# kulgurpowerMCU.net
KiCad netlist of a schematic drawn in EAGLE
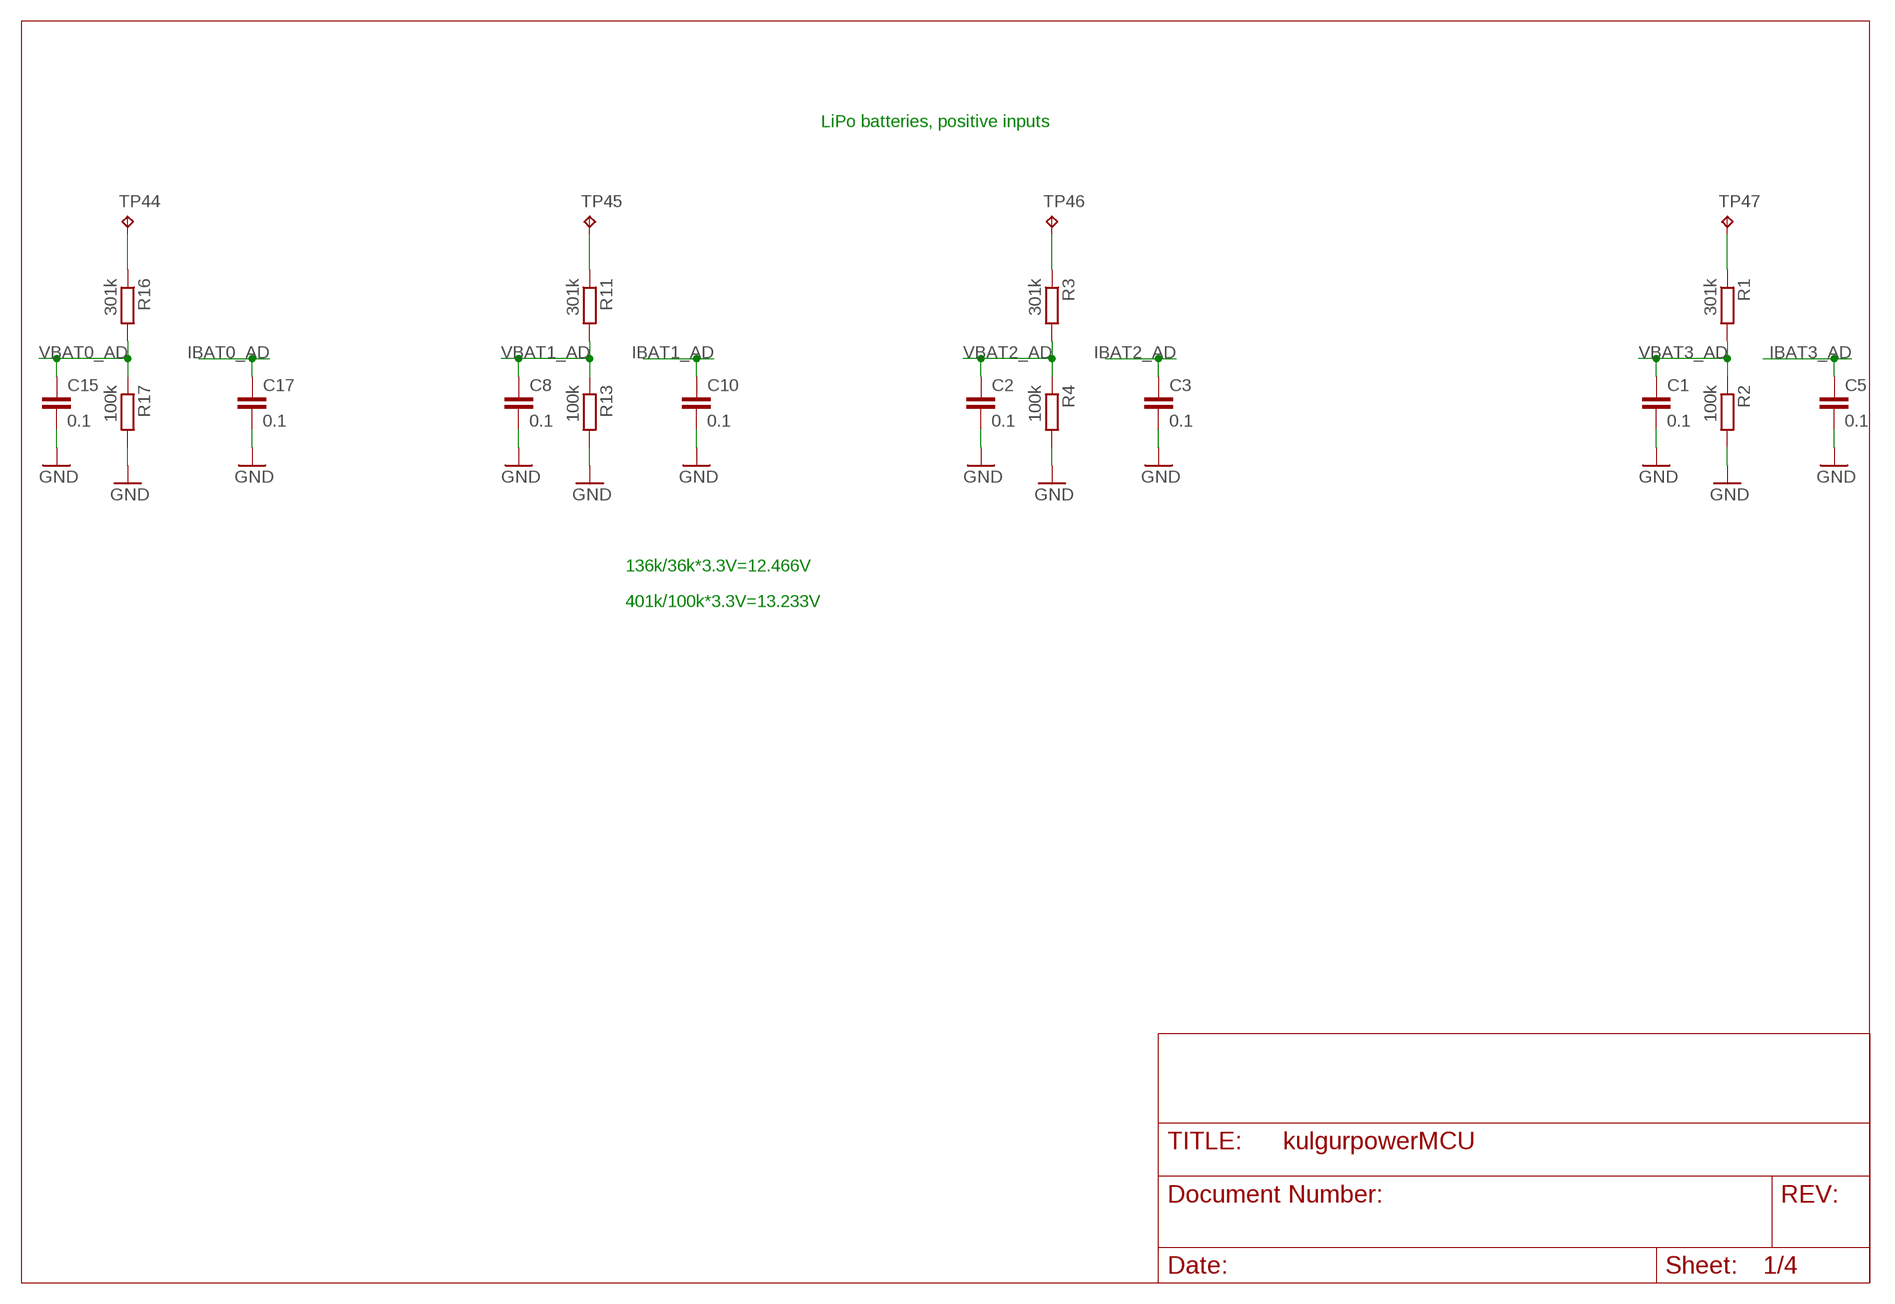
[diagram p0: schematic, sheet 1]
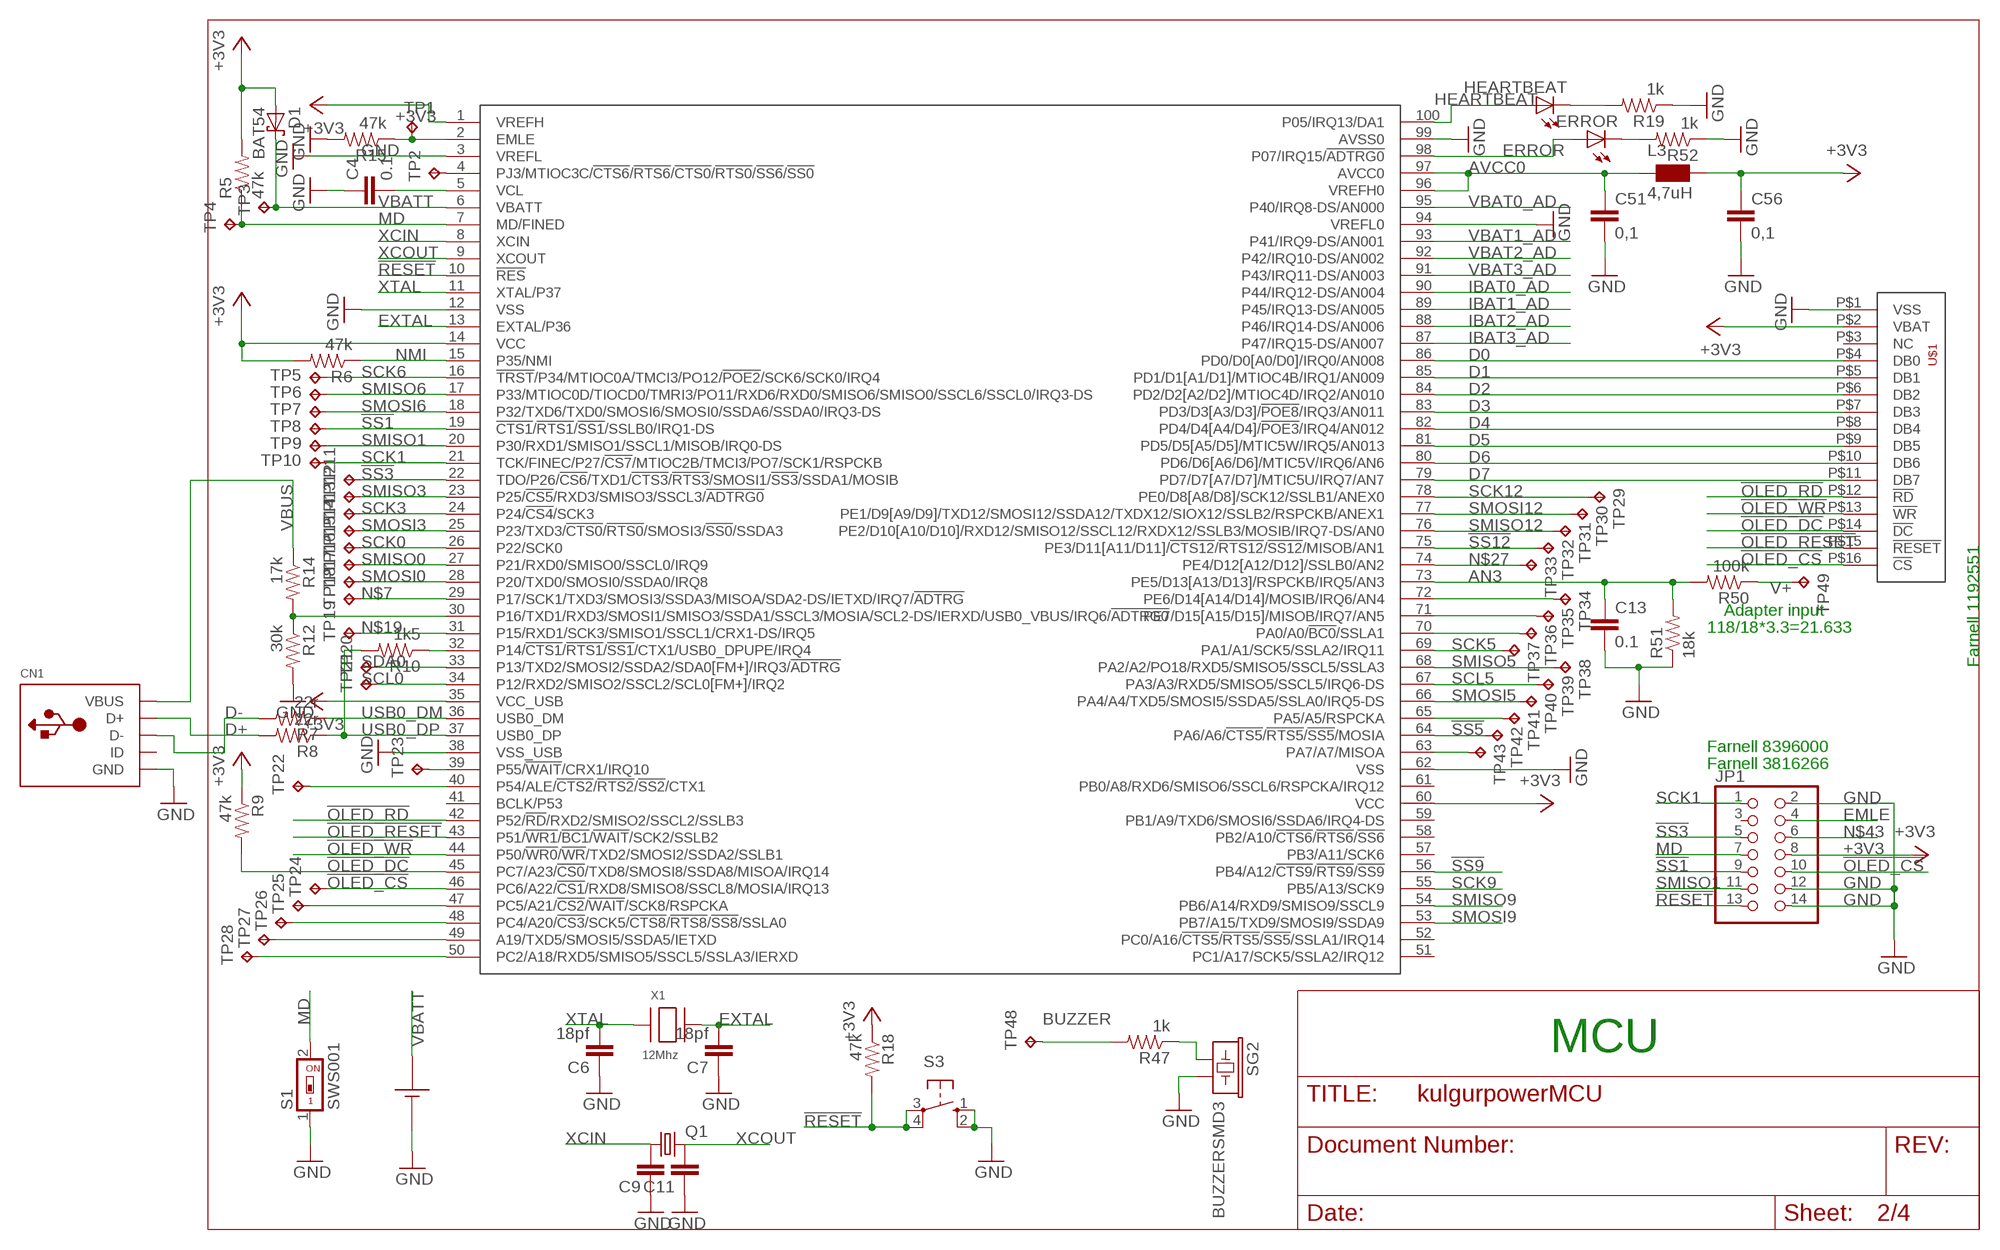
[diagram p1: schematic, sheet 2]
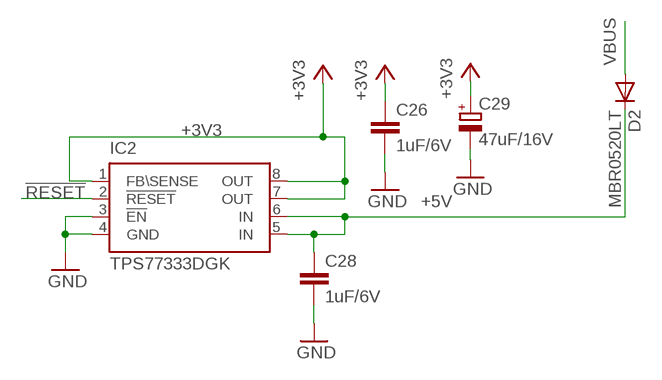
[diagram p2: schematic, sheet 3]

(export (version "E")
  (design (tool "Eeschema 10.0.6"))
  (components
    (comp (ref "C4")
      (value "0.1")
      (footprint "eagle-import:0603-CAP")
      (libsource (lib "eagle-import") (part "CAP0603-CAP"))
    )
    (comp (ref "C6")
      (value "18pf")
      (footprint "eagle-import:0603-CAP")
      (libsource (lib "eagle-import") (part "CAP0603-CAP"))
    )
    (comp (ref "C7")
      (value "18pf")
      (footprint "eagle-import:0603-CAP")
      (libsource (lib "eagle-import") (part "CAP0603-CAP"))
    )
    (comp (ref "C9")
      (value "CAP0603-CAP")
      (footprint "eagle-import:0603-CAP")
      (libsource (lib "eagle-import") (part "CAP0603-CAP"))
    )
    (comp (ref "C11")
      (value "CAP0603-CAP")
      (footprint "eagle-import:0603-CAP")
      (libsource (lib "eagle-import") (part "CAP0603-CAP"))
    )
    (comp (ref "C13")
      (value "0.1")
      (footprint "eagle-import:0603-CAP")
      (libsource (lib "eagle-import") (part "CAP0603-CAP"))
    )
    (comp (ref "C51")
      (value "0,1")
      (footprint "eagle-import:0603-CAP")
      (libsource (lib "eagle-import") (part "CAP0603-CAP"))
    )
    (comp (ref "C56")
      (value "0,1")
      (footprint "eagle-import:0603-CAP")
      (libsource (lib "eagle-import") (part "CAP0603-CAP"))
    )
    (comp (ref "CN1")
      (value "USBMINIB")
      (footprint "eagle-import:USB-MINIB")
      (libsource (lib "eagle-import") (part "USBMINIB"))
    )
    (comp (ref "D1")
      (value "BAT54")
      (footprint "eagle-import:SOT23")
      (libsource (lib "eagle-import") (part "BAT54"))
    )
    (comp (ref "ERROR")
      (value "LED0603")
      (footprint "eagle-import:LED-0603")
      (libsource (lib "eagle-import") (part "LED0603"))
    )
    (comp (ref "HEARTBEAT")
      (value "LED0603")
      (footprint "eagle-import:LED-0603")
      (libsource (lib "eagle-import") (part "LED0603"))
    )
    (comp (ref "JP1")
      (value "PINHD-2X7")
      (footprint "eagle-import:2X07")
      (libsource (lib "eagle-import") (part "PINHD-2X7"))
    )
    (comp (ref "L3")
      (value "4,7uH")
      (footprint "eagle-import:WE-KI_0805_B")
      (libsource (lib "eagle-import") (part "WE-KIHQ_0805"))
    )
    (comp (ref "Q1")
      (value "CRYSTALMM20SS")
      (footprint "eagle-import:MM20SS")
      (libsource (lib "eagle-import") (part "CRYSTALMM20SS"))
    )
    (comp (ref "R5")
      (value "47k")
      (footprint "eagle-import:0603-RES")
      (libsource (lib "eagle-import") (part "RESISTOR0603-RES"))
    )
    (comp (ref "R6")
      (value "47k")
      (footprint "eagle-import:0603-RES")
      (libsource (lib "eagle-import") (part "RESISTOR0603-RES"))
    )
    (comp (ref "R7")
      (value "22r")
      (footprint "eagle-import:0603-RES")
      (libsource (lib "eagle-import") (part "RESISTOR0603-RES"))
    )
    (comp (ref "R8")
      (value "22r")
      (footprint "eagle-import:0603-RES")
      (libsource (lib "eagle-import") (part "RESISTOR0603-RES"))
    )
    (comp (ref "R9")
      (value "47k")
      (footprint "eagle-import:0603-RES")
      (libsource (lib "eagle-import") (part "RESISTOR0603-RES"))
    )
    (comp (ref "R10")
      (value "1k5")
      (footprint "eagle-import:0603-RES")
      (libsource (lib "eagle-import") (part "RESISTOR0603-RES"))
    )
    (comp (ref "R12")
      (value "30k")
      (footprint "eagle-import:0603-RES")
      (libsource (lib "eagle-import") (part "RESISTOR0603-RES"))
    )
    (comp (ref "R14")
      (value "17k")
      (footprint "eagle-import:0603-RES")
      (libsource (lib "eagle-import") (part "RESISTOR0603-RES"))
    )
    (comp (ref "R15")
      (value "47k")
      (footprint "eagle-import:0603-RES")
      (libsource (lib "eagle-import") (part "RESISTOR0603-RES"))
    )
    (comp (ref "R18")
      (value "47k")
      (footprint "eagle-import:0603-RES")
      (libsource (lib "eagle-import") (part "RESISTOR0603-RES"))
    )
    (comp (ref "R19")
      (value "1k")
      (footprint "eagle-import:0603-RES")
      (libsource (lib "eagle-import") (part "RESISTOR0603-RES"))
    )
    (comp (ref "R47")
      (value "1k")
      (footprint "eagle-import:0603-RES")
      (libsource (lib "eagle-import") (part "RESISTOR0603-RES"))
    )
    (comp (ref "R50")
      (value "100k")
      (footprint "eagle-import:0603-RES")
      (libsource (lib "eagle-import") (part "RESISTOR0603-RES"))
    )
    (comp (ref "R51")
      (value "18k")
      (footprint "eagle-import:0603-RES")
      (libsource (lib "eagle-import") (part "RESISTOR0603-RES"))
    )
    (comp (ref "R52")
      (value "1k")
      (footprint "eagle-import:0603-RES")
      (libsource (lib "eagle-import") (part "RESISTOR0603-RES"))
    )
    (comp (ref "S1")
      (value "SWS001")
      (footprint "eagle-import:SMS-001")
      (libsource (lib "eagle-import") (part "SWS001"))
    )
    (comp (ref "S3")
      (value "10-XX")
      (footprint "eagle-import:B3F-10XX")
      (fields (field (name "MPN") "B3F-1000"))
      (libsource (lib "eagle-import") (part "10-XX"))
    )
    (comp (ref "SG2")
      (value "BUZZERSMD3")
      (footprint "eagle-import:BUZZER-CMT1102")
      (libsource (lib "eagle-import") (part "BUZZERSMD3"))
    )
    (comp (ref "TP1")
      (value "TPB2,54")
      (footprint "eagle-import:B2,54")
      (libsource (lib "eagle-import") (part "TPB2,54"))
    )
    (comp (ref "TP2")
      (value "TPB2,54")
      (footprint "eagle-import:B2,54")
      (libsource (lib "eagle-import") (part "TPB2,54"))
    )
    (comp (ref "TP3")
      (value "TPB2,54")
      (footprint "eagle-import:B2,54")
      (libsource (lib "eagle-import") (part "TPB2,54"))
    )
    (comp (ref "TP4")
      (value "TPB2,54")
      (footprint "eagle-import:B2,54")
      (libsource (lib "eagle-import") (part "TPB2,54"))
    )
    (comp (ref "TP5")
      (value "TPB1,27")
      (footprint "eagle-import:B1,27")
      (libsource (lib "eagle-import") (part "TPB1,27"))
    )
    (comp (ref "TP6")
      (value "TPB1,27")
      (footprint "eagle-import:B1,27")
      (libsource (lib "eagle-import") (part "TPB1,27"))
    )
    (comp (ref "TP7")
      (value "TPB1,27")
      (footprint "eagle-import:B1,27")
      (libsource (lib "eagle-import") (part "TPB1,27"))
    )
    (comp (ref "TP8")
      (value "TPB1,27")
      (footprint "eagle-import:B1,27")
      (libsource (lib "eagle-import") (part "TPB1,27"))
    )
    (comp (ref "TP9")
      (value "TPB1,27")
      (footprint "eagle-import:B1,27")
      (libsource (lib "eagle-import") (part "TPB1,27"))
    )
    (comp (ref "TP10")
      (value "TPB1,27")
      (footprint "eagle-import:B1,27")
      (libsource (lib "eagle-import") (part "TPB1,27"))
    )
    (comp (ref "TP11")
      (value "TPB1,27")
      (footprint "eagle-import:B1,27")
      (libsource (lib "eagle-import") (part "TPB1,27"))
    )
    (comp (ref "TP12")
      (value "TPB1,27")
      (footprint "eagle-import:B1,27")
      (libsource (lib "eagle-import") (part "TPB1,27"))
    )
    (comp (ref "TP13")
      (value "TPB1,27")
      (footprint "eagle-import:B1,27")
      (libsource (lib "eagle-import") (part "TPB1,27"))
    )
    (comp (ref "TP14")
      (value "TPB1,27")
      (footprint "eagle-import:B1,27")
      (libsource (lib "eagle-import") (part "TPB1,27"))
    )
    (comp (ref "TP15")
      (value "TPB1,27")
      (footprint "eagle-import:B1,27")
      (libsource (lib "eagle-import") (part "TPB1,27"))
    )
    (comp (ref "TP16")
      (value "TPB1,27")
      (footprint "eagle-import:B1,27")
      (libsource (lib "eagle-import") (part "TPB1,27"))
    )
    (comp (ref "TP17")
      (value "TPB1,27")
      (footprint "eagle-import:B1,27")
      (libsource (lib "eagle-import") (part "TPB1,27"))
    )
    (comp (ref "TP18")
      (value "TPB1,27")
      (footprint "eagle-import:B1,27")
      (libsource (lib "eagle-import") (part "TPB1,27"))
    )
    (comp (ref "TP19")
      (value "TPB1,27")
      (footprint "eagle-import:B1,27")
      (libsource (lib "eagle-import") (part "TPB1,27"))
    )
    (comp (ref "TP20")
      (value "TPB1,27")
      (footprint "eagle-import:B1,27")
      (libsource (lib "eagle-import") (part "TPB1,27"))
    )
    (comp (ref "TP21")
      (value "TPB1,27")
      (footprint "eagle-import:B1,27")
      (libsource (lib "eagle-import") (part "TPB1,27"))
    )
    (comp (ref "TP22")
      (value "TPB1,27")
      (footprint "eagle-import:B1,27")
      (libsource (lib "eagle-import") (part "TPB1,27"))
    )
    (comp (ref "TP23")
      (value "TPB1,27")
      (footprint "eagle-import:B1,27")
      (libsource (lib "eagle-import") (part "TPB1,27"))
    )
    (comp (ref "TP24")
      (value "TPB1,27")
      (footprint "eagle-import:B1,27")
      (libsource (lib "eagle-import") (part "TPB1,27"))
    )
    (comp (ref "TP25")
      (value "TPB1,27")
      (footprint "eagle-import:B1,27")
      (libsource (lib "eagle-import") (part "TPB1,27"))
    )
    (comp (ref "TP26")
      (value "TPB1,27")
      (footprint "eagle-import:B1,27")
      (libsource (lib "eagle-import") (part "TPB1,27"))
    )
    (comp (ref "TP27")
      (value "TPB1,27")
      (footprint "eagle-import:B1,27")
      (libsource (lib "eagle-import") (part "TPB1,27"))
    )
    (comp (ref "TP28")
      (value "TPB1,27")
      (footprint "eagle-import:B1,27")
      (libsource (lib "eagle-import") (part "TPB1,27"))
    )
    (comp (ref "TP29")
      (value "TPB1,27")
      (footprint "eagle-import:B1,27")
      (libsource (lib "eagle-import") (part "TPB1,27"))
    )
    (comp (ref "TP30")
      (value "TPB1,27")
      (footprint "eagle-import:B1,27")
      (libsource (lib "eagle-import") (part "TPB1,27"))
    )
    (comp (ref "TP31")
      (value "TPB1,27")
      (footprint "eagle-import:B1,27")
      (libsource (lib "eagle-import") (part "TPB1,27"))
    )
    (comp (ref "TP32")
      (value "TPB1,27")
      (footprint "eagle-import:B1,27")
      (libsource (lib "eagle-import") (part "TPB1,27"))
    )
    (comp (ref "TP33")
      (value "TPB1,27")
      (footprint "eagle-import:B1,27")
      (libsource (lib "eagle-import") (part "TPB1,27"))
    )
    (comp (ref "TP34")
      (value "TPB1,27")
      (footprint "eagle-import:B1,27")
      (libsource (lib "eagle-import") (part "TPB1,27"))
    )
    (comp (ref "TP35")
      (value "TPB1,27")
      (footprint "eagle-import:B1,27")
      (libsource (lib "eagle-import") (part "TPB1,27"))
    )
    (comp (ref "TP36")
      (value "TPB1,27")
      (footprint "eagle-import:B1,27")
      (libsource (lib "eagle-import") (part "TPB1,27"))
    )
    (comp (ref "TP37")
      (value "TPB1,27")
      (footprint "eagle-import:B1,27")
      (libsource (lib "eagle-import") (part "TPB1,27"))
    )
    (comp (ref "TP38")
      (value "TPB1,27")
      (footprint "eagle-import:B1,27")
      (libsource (lib "eagle-import") (part "TPB1,27"))
    )
    (comp (ref "TP39")
      (value "TPB1,27")
      (footprint "eagle-import:B1,27")
      (libsource (lib "eagle-import") (part "TPB1,27"))
    )
    (comp (ref "TP40")
      (value "TPB1,27")
      (footprint "eagle-import:B1,27")
      (libsource (lib "eagle-import") (part "TPB1,27"))
    )
    (comp (ref "TP41")
      (value "TPB1,27")
      (footprint "eagle-import:B1,27")
      (libsource (lib "eagle-import") (part "TPB1,27"))
    )
    (comp (ref "TP42")
      (value "TPB1,27")
      (footprint "eagle-import:B1,27")
      (libsource (lib "eagle-import") (part "TPB1,27"))
    )
    (comp (ref "TP43")
      (value "TPB1,27")
      (footprint "eagle-import:B1,27")
      (libsource (lib "eagle-import") (part "TPB1,27"))
    )
    (comp (ref "TP48")
      (value "TPB1,27")
      (footprint "eagle-import:B1,27")
      (libsource (lib "eagle-import") (part "TPB1,27"))
    )
    (comp (ref "TP49")
      (value "TPB1,27")
      (footprint "eagle-import:B1,27")
      (libsource (lib "eagle-import") (part "TPB1,27"))
    )
    (comp (ref "U$1")
      (value "ER-OLEDM032-1")
      (footprint "eagle-import:ER-OLEDM032-1")
      (libsource (lib "eagle-import") (part "ER-OLEDM032-1"))
    )
    (comp (ref "U$2")
      (value "EDLRD224V3R6C")
      (footprint "eagle-import:EDLRD224V3R6C")
      (libsource (lib "eagle-import") (part "EDLRD224V3R6C"))
    )
    (comp (ref "U$14")
      (value "R5F5630ADDFP")
      (footprint "eagle-import:LTQFP100")
      (libsource (lib "eagle-import") (part "R5F5630ADDFP"))
    )
    (comp (ref "X1")
      (value "12Mhz")
      (footprint "eagle-import:NX5032")
      (libsource (lib "eagle-import") (part "XTALNX5032"))
    )
    (comp (ref "C26")
      (value "1uF/6V")
      (footprint "eagle-import:C0603")
      (libsource (lib "eagle-import") (part "resistor_C-EUC0603"))
    )
    (comp (ref "C28")
      (value "1uF/6V")
      (footprint "eagle-import:C0603")
      (libsource (lib "eagle-import") (part "resistor_C-EUC0603"))
    )
    (comp (ref "C29")
      (value "47uF/16V")
      (footprint "eagle-import:C_6032-28R")
      (libsource (lib "eagle-import") (part "CPOL-EUC/6032-28R"))
    )
    (comp (ref "D2")
      (value "MBR0520LT")
      (footprint "eagle-import:SOD123")
      (libsource (lib "eagle-import") (part "MBR0520LT"))
    )
    (comp (ref "IC2")
      (value "TPS77333DGK")
      (footprint "eagle-import:MSOP8")
      (libsource (lib "eagle-import") (part "TPS773"))
    )
    (comp (ref "C1")
      (value "0.1")
      (footprint "eagle-import:C0603")
      (libsource (lib "eagle-import") (part "C-EUC0603"))
    )
    (comp (ref "C2")
      (value "0.1")
      (footprint "eagle-import:C0603")
      (libsource (lib "eagle-import") (part "C-EUC0603"))
    )
    (comp (ref "C3")
      (value "0.1")
      (footprint "eagle-import:C0603")
      (libsource (lib "eagle-import") (part "C-EUC0603"))
    )
    (comp (ref "C5")
      (value "0.1")
      (footprint "eagle-import:C0603")
      (libsource (lib "eagle-import") (part "C-EUC0603"))
    )
    (comp (ref "C8")
      (value "0.1")
      (footprint "eagle-import:C0603")
      (libsource (lib "eagle-import") (part "C-EUC0603"))
    )
    (comp (ref "C10")
      (value "0.1")
      (footprint "eagle-import:C0603")
      (libsource (lib "eagle-import") (part "C-EUC0603"))
    )
    (comp (ref "C15")
      (value "0.1")
      (footprint "eagle-import:C0603")
      (libsource (lib "eagle-import") (part "C-EUC0603"))
    )
    (comp (ref "C17")
      (value "0.1")
      (footprint "eagle-import:C0603")
      (libsource (lib "eagle-import") (part "C-EUC0603"))
    )
    (comp (ref "R1")
      (value "301k")
      (footprint "eagle-import:R0603")
      (libsource (lib "eagle-import") (part "R-EU_R0603"))
    )
    (comp (ref "R2")
      (value "100k")
      (footprint "eagle-import:R0603")
      (libsource (lib "eagle-import") (part "R-EU_R0603"))
    )
    (comp (ref "R3")
      (value "301k")
      (footprint "eagle-import:R0603")
      (libsource (lib "eagle-import") (part "R-EU_R0603"))
    )
    (comp (ref "R4")
      (value "100k")
      (footprint "eagle-import:R0603")
      (libsource (lib "eagle-import") (part "R-EU_R0603"))
    )
    (comp (ref "R11")
      (value "301k")
      (footprint "eagle-import:R0603")
      (libsource (lib "eagle-import") (part "R-EU_R0603"))
    )
    (comp (ref "R13")
      (value "100k")
      (footprint "eagle-import:R0603")
      (libsource (lib "eagle-import") (part "R-EU_R0603"))
    )
    (comp (ref "R16")
      (value "301k")
      (footprint "eagle-import:R0603")
      (libsource (lib "eagle-import") (part "R-EU_R0603"))
    )
    (comp (ref "R17")
      (value "100k")
      (footprint "eagle-import:R0603")
      (libsource (lib "eagle-import") (part "R-EU_R0603"))
    )
    (comp (ref "TP44")
      (value "TPB1,27")
      (footprint "eagle-import:B1,27")
      (libsource (lib "eagle-import") (part "TPB1,27"))
    )
    (comp (ref "TP45")
      (value "TPB1,27")
      (footprint "eagle-import:B1,27")
      (libsource (lib "eagle-import") (part "TPB1,27"))
    )
    (comp (ref "TP46")
      (value "TPB1,27")
      (footprint "eagle-import:B1,27")
      (libsource (lib "eagle-import") (part "TPB1,27"))
    )
    (comp (ref "TP47")
      (value "TPB1,27")
      (footprint "eagle-import:B1,27")
      (libsource (lib "eagle-import") (part "TPB1,27"))
    )
  )
  (nets
    (net (code "1") (name "+3V3") (class "Default")
      (node (ref "C26") (pin "1") (pinfunction "1_1") (pintype "passive"))
      (node (ref "C29") (pin "+") (pinfunction "+_+") (pintype "passive"))
      (node (ref "C56") (pin "1") (pinfunction "1_1") (pintype "passive"))
      (node (ref "D1") (pin "1") (pinfunction "A_1") (pintype "passive"))
      (node (ref "IC2") (pin "1") (pinfunction "FB\\SENSE_1") (pintype "input"))
      (node (ref "IC2") (pin "7") (pinfunction "OUT_7") (pintype "output"))
      (node (ref "IC2") (pin "8") (pinfunction "OUT_8") (pintype "passive"))
      (node (ref "JP1") (pin "8") (pinfunction "8_8") (pintype "passive"))
      (node (ref "L3") (pin "1") (pinfunction "2_1") (pintype "passive"))
      (node (ref "R18") (pin "1") (pinfunction "1_1") (pintype "passive"))
      (node (ref "R5") (pin "2") (pinfunction "2_2") (pintype "passive"))
      (node (ref "R6") (pin "2") (pinfunction "2_2") (pintype "passive"))
      (node (ref "R9") (pin "1") (pinfunction "1_1") (pintype "passive"))
      (node (ref "U$1") (pin "P$2") (pinfunction "VBAT_P$2") (pintype "bidirectional"))
      (node (ref "U$14") (pin "1") (pinfunction "VREFH_1") (pintype "bidirectional"))
      (node (ref "U$14") (pin "14") (pinfunction "VCC_14") (pintype "bidirectional"))
      (node (ref "U$14") (pin "35") (pinfunction "VCC_USB_35") (pintype "bidirectional"))
      (node (ref "U$14") (pin "60") (pinfunction "VCC_60") (pintype "bidirectional"))
    )
    (net (code "2") (name "+5V") (class "Default")
      (node (ref "C28") (pin "1") (pinfunction "1_1") (pintype "passive"))
      (node (ref "D2") (pin "C") (pinfunction "C_C") (pintype "passive"))
      (node (ref "IC2") (pin "5") (pinfunction "IN_5") (pintype "input"))
      (node (ref "IC2") (pin "6") (pinfunction "IN_6") (pintype "input"))
    )
    (net (code "3") (name "AN3") (class "Default")
      (node (ref "C13") (pin "1") (pinfunction "1_1") (pintype "passive"))
      (node (ref "R50") (pin "2") (pinfunction "2_2") (pintype "passive"))
      (node (ref "R51") (pin "2") (pinfunction "2_2") (pintype "passive"))
      (node (ref "U$14") (pin "73") (pinfunction "PE5/D13[A13/D13]/RSPCKB/IRQ5/AN3_73") (pintype "bidirectional"))
    )
    (net (code "4") (name "AVCC0") (class "Default")
      (node (ref "C51") (pin "1") (pinfunction "1_1") (pintype "passive"))
      (node (ref "L3") (pin "2") (pinfunction "1_2") (pintype "passive"))
      (node (ref "U$14") (pin "96") (pinfunction "VREFH0_96") (pintype "bidirectional"))
      (node (ref "U$14") (pin "97") (pinfunction "AVCC0_97") (pintype "bidirectional"))
    )
    (net (code "5") (name "BUZZER") (class "Default")
      (node (ref "R47") (pin "2") (pinfunction "2_2") (pintype "passive"))
      (node (ref "TP48") (pin "TP") (pinfunction "TP_TP") (pintype "input"))
    )
    (net (code "6") (name "D+") (class "Default")
      (node (ref "CN1") (pin "D+") (pinfunction "D+_D+") (pintype "bidirectional"))
      (node (ref "R8") (pin "2") (pinfunction "2_2") (pintype "passive"))
    )
    (net (code "7") (name "D-") (class "Default")
      (node (ref "CN1") (pin "D-") (pinfunction "D-_D-") (pintype "bidirectional"))
      (node (ref "R7") (pin "2") (pinfunction "2_2") (pintype "passive"))
    )
    (net (code "8") (name "D0") (class "Default")
      (node (ref "U$1") (pin "P$4") (pinfunction "DB0_P$4") (pintype "bidirectional"))
      (node (ref "U$14") (pin "86") (pinfunction "PD0/D0[A0/D0]/IRQ0/AN008_86") (pintype "bidirectional"))
    )
    (net (code "9") (name "D1") (class "Default")
      (node (ref "U$1") (pin "P$5") (pinfunction "DB1_P$5") (pintype "bidirectional"))
      (node (ref "U$14") (pin "85") (pinfunction "PD1/D1[A1/D1]/MTIOC4B/IRQ1/AN009_85") (pintype "bidirectional"))
    )
    (net (code "10") (name "D2") (class "Default")
      (node (ref "U$1") (pin "P$6") (pinfunction "DB2_P$6") (pintype "bidirectional"))
      (node (ref "U$14") (pin "84") (pinfunction "PD2/D2[A2/D2]/MTIOC4D/IRQ2/AN010_84") (pintype "bidirectional"))
    )
    (net (code "11") (name "D3") (class "Default")
      (node (ref "U$1") (pin "P$7") (pinfunction "DB3_P$7") (pintype "bidirectional"))
      (node (ref "U$14") (pin "83") (pinfunction "PD3/D3[A3/D3]/~{POE8}/IRQ3/AN011_83") (pintype "bidirectional"))
    )
    (net (code "12") (name "D4") (class "Default")
      (node (ref "U$1") (pin "P$8") (pinfunction "DB4_P$8") (pintype "bidirectional"))
      (node (ref "U$14") (pin "82") (pinfunction "PD4/D4[A4/D4]/~{POE3}/IRQ4/AN012_82") (pintype "bidirectional"))
    )
    (net (code "13") (name "D5") (class "Default")
      (node (ref "U$1") (pin "P$9") (pinfunction "DB5_P$9") (pintype "bidirectional"))
      (node (ref "U$14") (pin "81") (pinfunction "PD5/D5[A5/D5]/MTIC5W/IRQ5/AN013_81") (pintype "bidirectional"))
    )
    (net (code "14") (name "D6") (class "Default")
      (node (ref "U$1") (pin "P$10") (pinfunction "DB6_P$10") (pintype "bidirectional"))
      (node (ref "U$14") (pin "80") (pinfunction "PD6/D6[A6/D6]/MTIC5V/IRQ6/AN6_80") (pintype "bidirectional"))
    )
    (net (code "15") (name "D7") (class "Default")
      (node (ref "U$1") (pin "P$11") (pinfunction "DB7_P$11") (pintype "bidirectional"))
      (node (ref "U$14") (pin "79") (pinfunction "PD7/D7[A7/D7]/MTIC5U/IRQ7/AN7_79") (pintype "bidirectional"))
    )
    (net (code "16") (name "EMLE") (class "Default")
      (node (ref "JP1") (pin "4") (pinfunction "4_4") (pintype "passive"))
      (node (ref "R15") (pin "1") (pinfunction "1_1") (pintype "passive"))
      (node (ref "TP1") (pin "TP") (pinfunction "TP_TP") (pintype "input"))
      (node (ref "U$14") (pin "2") (pinfunction "EMLE_2") (pintype "bidirectional"))
    )
    (net (code "17") (name "ERROR") (class "Default")
      (node (ref "ERROR") (pin "A") (pinfunction "A_A") (pintype "passive"))
      (node (ref "U$14") (pin "98") (pinfunction "P07/IRQ15/~{ADTRG0}_98") (pintype "bidirectional"))
    )
    (net (code "18") (name "EXTAL") (class "Default")
      (node (ref "C7") (pin "2") (pinfunction "2_2") (pintype "passive"))
      (node (ref "U$14") (pin "13") (pinfunction "EXTAL/P36_13") (pintype "bidirectional"))
      (node (ref "X1") (pin "P$2") (pinfunction "P$2_P$2") (pintype "bidirectional"))
    )
    (net (code "19") (name "GND") (class "Default")
      (node (ref "C1") (pin "2") (pinfunction "2_2") (pintype "passive"))
      (node (ref "C10") (pin "2") (pinfunction "2_2") (pintype "passive"))
      (node (ref "C11") (pin "1") (pinfunction "1_1") (pintype "passive"))
      (node (ref "C13") (pin "2") (pinfunction "2_2") (pintype "passive"))
      (node (ref "C15") (pin "2") (pinfunction "2_2") (pintype "passive"))
      (node (ref "C17") (pin "2") (pinfunction "2_2") (pintype "passive"))
      (node (ref "C2") (pin "2") (pinfunction "2_2") (pintype "passive"))
      (node (ref "C26") (pin "2") (pinfunction "2_2") (pintype "passive"))
      (node (ref "C28") (pin "2") (pinfunction "2_2") (pintype "passive"))
      (node (ref "C29") (pin "-") (pinfunction "-_-") (pintype "passive"))
      (node (ref "C3") (pin "2") (pinfunction "2_2") (pintype "passive"))
      (node (ref "C4") (pin "1") (pinfunction "1_1") (pintype "passive"))
      (node (ref "C5") (pin "2") (pinfunction "2_2") (pintype "passive"))
      (node (ref "C51") (pin "2") (pinfunction "2_2") (pintype "passive"))
      (node (ref "C56") (pin "2") (pinfunction "2_2") (pintype "passive"))
      (node (ref "C6") (pin "1") (pinfunction "1_1") (pintype "passive"))
      (node (ref "C7") (pin "1") (pinfunction "1_1") (pintype "passive"))
      (node (ref "C8") (pin "2") (pinfunction "2_2") (pintype "passive"))
      (node (ref "C9") (pin "1") (pinfunction "1_1") (pintype "passive"))
      (node (ref "CN1") (pin "GND") (pinfunction "GND_GND") (pintype "power_in"))
      (node (ref "IC2") (pin "3") (pinfunction "~{EN}_3") (pintype "input"))
      (node (ref "IC2") (pin "4") (pinfunction "GND_4") (pintype "power_in"))
      (node (ref "JP1") (pin "12") (pinfunction "12_12") (pintype "passive"))
      (node (ref "JP1") (pin "14") (pinfunction "14_14") (pintype "passive"))
      (node (ref "JP1") (pin "2") (pinfunction "2_2") (pintype "passive"))
      (node (ref "R12") (pin "2") (pinfunction "2_2") (pintype "passive"))
      (node (ref "R13") (pin "2") (pinfunction "2_2") (pintype "passive"))
      (node (ref "R15") (pin "2") (pinfunction "2_2") (pintype "passive"))
      (node (ref "R17") (pin "2") (pinfunction "2_2") (pintype "passive"))
      (node (ref "R19") (pin "1") (pinfunction "1_1") (pintype "passive"))
      (node (ref "R2") (pin "2") (pinfunction "2_2") (pintype "passive"))
      (node (ref "R4") (pin "2") (pinfunction "2_2") (pintype "passive"))
      (node (ref "R51") (pin "1") (pinfunction "1_1") (pintype "passive"))
      (node (ref "R52") (pin "1") (pinfunction "1_1") (pintype "passive"))
      (node (ref "S1") (pin "1") (pinfunction "1_1") (pintype "passive"))
      (node (ref "S3") (pin "1") (pinfunction "S_1") (pintype "passive"))
      (node (ref "S3") (pin "2") (pinfunction "S1_2") (pintype "passive"))
      (node (ref "SG2") (pin "2") (pinfunction "2_2") (pintype "passive"))
      (node (ref "U$1") (pin "P$1") (pinfunction "VSS_P$1") (pintype "bidirectional"))
      (node (ref "U$14") (pin "12") (pinfunction "VSS_12") (pintype "bidirectional"))
      (node (ref "U$14") (pin "3") (pinfunction "VREFL_3") (pintype "bidirectional"))
      (node (ref "U$14") (pin "38") (pinfunction "VSS_USB_38") (pintype "bidirectional"))
      (node (ref "U$14") (pin "62") (pinfunction "VSS_62") (pintype "bidirectional"))
      (node (ref "U$14") (pin "94") (pinfunction "VREFL0_94") (pintype "bidirectional"))
      (node (ref "U$14") (pin "99") (pinfunction "AVSS0_99") (pintype "bidirectional"))
      (node (ref "U$2") (pin "N") (pinfunction "N_N") (pintype "bidirectional"))
    )
    (net (code "20") (name "HEARTBEAT") (class "Default")
      (node (ref "HEARTBEAT") (pin "A") (pinfunction "A_A") (pintype "passive"))
      (node (ref "U$14") (pin "100") (pinfunction "P05/IRQ13/DA1_100") (pintype "bidirectional"))
    )
    (net (code "21") (name "IBAT0_AD") (class "Default")
      (node (ref "C17") (pin "1") (pinfunction "1_1") (pintype "passive"))
      (node (ref "U$14") (pin "90") (pinfunction "P44/IRQ12-DS/AN004_90") (pintype "bidirectional"))
    )
    (net (code "22") (name "IBAT1_AD") (class "Default")
      (node (ref "C10") (pin "1") (pinfunction "1_1") (pintype "passive"))
      (node (ref "U$14") (pin "89") (pinfunction "P45/IRQ13-DS/AN005_89") (pintype "bidirectional"))
    )
    (net (code "23") (name "IBAT2_AD") (class "Default")
      (node (ref "C3") (pin "1") (pinfunction "1_1") (pintype "passive"))
      (node (ref "U$14") (pin "88") (pinfunction "P46/IRQ14-DS/AN006_88") (pintype "bidirectional"))
    )
    (net (code "24") (name "IBAT3_AD") (class "Default")
      (node (ref "C5") (pin "1") (pinfunction "1_1") (pintype "passive"))
      (node (ref "U$14") (pin "87") (pinfunction "P47/IRQ15-DS/AN007_87") (pintype "bidirectional"))
    )
    (net (code "25") (name "MD") (class "Default")
      (node (ref "JP1") (pin "7") (pinfunction "7_7") (pintype "passive"))
      (node (ref "R5") (pin "1") (pinfunction "1_1") (pintype "passive"))
      (node (ref "S1") (pin "2") (pinfunction "2_2") (pintype "passive"))
      (node (ref "TP4") (pin "TP") (pinfunction "TP_TP") (pintype "input"))
      (node (ref "U$14") (pin "7") (pinfunction "MD/FINED_7") (pintype "bidirectional"))
    )
    (net (code "26") (name "N$7") (class "Default")
      (node (ref "TP18") (pin "TP") (pinfunction "TP_TP") (pintype "input"))
      (node (ref "U$14") (pin "29") (pinfunction "P17/SCK1/TXD3/SMOSI3/SSDA3/MISOA/SDA2-DS/IETXD/IRQ7/~{ADTRG}_29") (pintype "bidirectional"))
    )
    (net (code "27") (name "N$19") (class "Default")
      (node (ref "TP19") (pin "TP") (pinfunction "TP_TP") (pintype "input"))
      (node (ref "U$14") (pin "31") (pinfunction "P15/RXD1/SCK3/SMISO1/SSCL1/CRX1-DS/IRQ5_31") (pintype "bidirectional"))
    )
    (net (code "28") (name "N$27") (class "Default")
      (node (ref "TP33") (pin "TP") (pinfunction "TP_TP") (pintype "input"))
      (node (ref "U$14") (pin "74") (pinfunction "PE4/D12[A12/D12]/SSLB0/AN2_74") (pintype "bidirectional"))
    )
    (net (code "29") (name "N$43") (class "Default")
      (node (ref "JP1") (pin "6") (pinfunction "6_6") (pintype "passive"))
    )
    (net (code "30") (name "NMI") (class "Default")
      (node (ref "R6") (pin "1") (pinfunction "1_1") (pintype "passive"))
      (node (ref "U$14") (pin "15") (pinfunction "P35/NMI_15") (pintype "bidirectional"))
    )
    (net (code "31") (name "Net-(ERROR-PadC)") (class "Default")
      (node (ref "ERROR") (pin "C") (pinfunction "C_C") (pintype "passive"))
      (node (ref "R52") (pin "2") (pinfunction "2_2") (pintype "passive"))
    )
    (net (code "32") (name "Net-(HEARTBEAT-PadC)") (class "Default")
      (node (ref "HEARTBEAT") (pin "C") (pinfunction "C_C") (pintype "passive"))
      (node (ref "R19") (pin "2") (pinfunction "2_2") (pintype "passive"))
    )
    (net (code "33") (name "Net-(R1-Pad1)") (class "Default")
      (node (ref "R1") (pin "1") (pinfunction "1_1") (pintype "passive"))
      (node (ref "TP47") (pin "TP") (pinfunction "TP_TP") (pintype "input"))
    )
    (net (code "34") (name "Net-(R3-Pad1)") (class "Default")
      (node (ref "R3") (pin "1") (pinfunction "1_1") (pintype "passive"))
      (node (ref "TP46") (pin "TP") (pinfunction "TP_TP") (pintype "input"))
    )
    (net (code "35") (name "Net-(R11-Pad1)") (class "Default")
      (node (ref "R11") (pin "1") (pinfunction "1_1") (pintype "passive"))
      (node (ref "TP45") (pin "TP") (pinfunction "TP_TP") (pintype "input"))
    )
    (net (code "36") (name "Net-(R16-Pad1)") (class "Default")
      (node (ref "R16") (pin "1") (pinfunction "1_1") (pintype "passive"))
      (node (ref "TP44") (pin "TP") (pinfunction "TP_TP") (pintype "input"))
    )
    (net (code "37") (name "Net-(R47-Pad1)") (class "Default")
      (node (ref "R47") (pin "1") (pinfunction "1_1") (pintype "passive"))
      (node (ref "SG2") (pin "1") (pinfunction "1_1") (pintype "passive"))
    )
    (net (code "38") (name "Net-(U$14-A19{slash}TXD5{slash}SMOSI5{slash}SSDA5{slash}IETXD)") (class "Default")
      (node (ref "TP27") (pin "TP") (pinfunction "TP_TP") (pintype "input"))
      (node (ref "U$14") (pin "49") (pinfunction "A19/TXD5/SMOSI5/SSDA5/IETXD_49") (pintype "bidirectional"))
    )
    (net (code "39") (name "Net-(U$14-P14{slash}~{CTS1}{slash}~{RTS1}{slash}~{SS1}{slash}CTX1{slash}USB0_DPUPE{slash}IRQ4)") (class "Default")
      (node (ref "R10") (pin "1") (pinfunction "1_1") (pintype "passive"))
      (node (ref "U$14") (pin "32") (pinfunction "P14/~{CTS1}/~{RTS1}/~{SS1}/CTX1/USB0_DPUPE/IRQ4_32") (pintype "bidirectional"))
    )
    (net (code "40") (name "Net-(U$14-P16{slash}TXD1{slash}RXD3{slash}SMOSI1{slash}SMISO3{slash}SSDA1{slash}SSCL3{slash}MOSIA{slash}SCL2-DS{slash}IERXD{slash}USB0_VBUS{slash}IRQ6{slash}~{ADTRG0})") (class "Default")
      (node (ref "R12") (pin "1") (pinfunction "1_1") (pintype "passive"))
      (node (ref "R14") (pin "2") (pinfunction "2_2") (pintype "passive"))
      (node (ref "U$14") (pin "30") (pinfunction "P16/TXD1/RXD3/SMOSI1/SMISO3/SSDA1/SSCL3/MOSIA/SCL2-DS/IERXD/USB0_VBUS/IRQ6/~{ADTRG0}_30") (pintype "bidirectional"))
    )
    (net (code "41") (name "Net-(U$14-P54{slash}ALE{slash}~{CTS2}{slash}~{RTS2}{slash}~{SS2}{slash}CTX1)") (class "Default")
      (node (ref "TP22") (pin "TP") (pinfunction "TP_TP") (pintype "input"))
      (node (ref "U$14") (pin "40") (pinfunction "P54/ALE/~{CTS2}/~{RTS2}/~{SS2}/CTX1_40") (pintype "bidirectional"))
    )
    (net (code "42") (name "Net-(U$14-P55{slash}~{WAIT}{slash}CRX1{slash}IRQ10)") (class "Default")
      (node (ref "TP23") (pin "TP") (pinfunction "TP_TP") (pintype "input"))
      (node (ref "U$14") (pin "39") (pinfunction "P55/~{WAIT}/CRX1/IRQ10_39") (pintype "bidirectional"))
    )
    (net (code "43") (name "Net-(U$14-PA0{slash}A0{slash}~{BC0}{slash}SSLA1)") (class "Default")
      (node (ref "TP36") (pin "TP") (pinfunction "TP_TP") (pintype "input"))
      (node (ref "U$14") (pin "70") (pinfunction "PA0/A0/~{BC0}/SSLA1_70") (pintype "bidirectional"))
    )
    (net (code "44") (name "Net-(U$14-PA5{slash}A5{slash}RSPCKA)") (class "Default")
      (node (ref "TP41") (pin "TP") (pinfunction "TP_TP") (pintype "input"))
      (node (ref "U$14") (pin "65") (pinfunction "PA5/A5/RSPCKA_65") (pintype "bidirectional"))
    )
    (net (code "45") (name "Net-(U$14-PA7{slash}A7{slash}MISOA)") (class "Default")
      (node (ref "TP43") (pin "TP") (pinfunction "TP_TP") (pintype "input"))
      (node (ref "U$14") (pin "63") (pinfunction "PA7/A7/MISOA_63") (pintype "bidirectional"))
    )
    (net (code "46") (name "Net-(U$14-PC2{slash}A18{slash}RXD5{slash}SMISO5{slash}SSCL5{slash}SSLA3{slash}IERXD)") (class "Default")
      (node (ref "TP28") (pin "TP") (pinfunction "TP_TP") (pintype "input"))
      (node (ref "U$14") (pin "50") (pinfunction "PC2/A18/RXD5/SMISO5/SSCL5/SSLA3/IERXD_50") (pintype "bidirectional"))
    )
    (net (code "47") (name "Net-(U$14-PC4{slash}A20{slash}~{CS3}{slash}SCK5{slash}~{CTS8}{slash}~{RTS8}{slash}~{SS8}{slash}SSLA0)") (class "Default")
      (node (ref "TP26") (pin "TP") (pinfunction "TP_TP") (pintype "input"))
      (node (ref "U$14") (pin "48") (pinfunction "PC4/A20/~{CS3}/SCK5/~{CTS8}/~{RTS8}/~{SS8}/SSLA0_48") (pintype "bidirectional"))
    )
    (net (code "48") (name "Net-(U$14-PC5{slash}A21{slash}~{CS2}{slash}~{WAIT}{slash}SCK8{slash}RSPCKA)") (class "Default")
      (node (ref "TP25") (pin "TP") (pinfunction "TP_TP") (pintype "input"))
      (node (ref "U$14") (pin "47") (pinfunction "PC5/A21/~{CS2}/~{WAIT}/SCK8/RSPCKA_47") (pintype "bidirectional"))
    )
    (net (code "49") (name "Net-(U$14-PE6{slash}D14[A14{slash}D14]{slash}MOSIB{slash}IRQ6{slash}AN4)") (class "Default")
      (node (ref "TP34") (pin "TP") (pinfunction "TP_TP") (pintype "input"))
      (node (ref "U$14") (pin "72") (pinfunction "PE6/D14[A14/D14]/MOSIB/IRQ6/AN4_72") (pintype "bidirectional"))
    )
    (net (code "50") (name "Net-(U$14-PE7{slash}D15[A15{slash}D15]{slash}MISOB{slash}IRQ7{slash}AN5)") (class "Default")
      (node (ref "TP35") (pin "TP") (pinfunction "TP_TP") (pintype "input"))
      (node (ref "U$14") (pin "71") (pinfunction "PE7/D15[A15/D15]/MISOB/IRQ7/AN5_71") (pintype "bidirectional"))
    )
    (net (code "51") (name "Net-(U$14-PJ3{slash}MTIOC3C{slash}~{CTS6}{slash}~{RTS6}{slash}~{CTS0}{slash}~{RTS0}{slash}~{SS6}{slash}~{SS0})") (class "Default")
      (node (ref "TP2") (pin "TP") (pinfunction "TP_TP") (pintype "input"))
      (node (ref "U$14") (pin "4") (pinfunction "PJ3/MTIOC3C/~{CTS6}/~{RTS6}/~{CTS0}/~{RTS0}/~{SS6}/~{SS0}_4") (pintype "bidirectional"))
    )
    (net (code "52") (name "Net-(U$14-VCL)") (class "Default")
      (node (ref "C4") (pin "2") (pinfunction "2_2") (pintype "passive"))
      (node (ref "U$14") (pin "5") (pinfunction "VCL_5") (pintype "bidirectional"))
    )
    (net (code "53") (name "SCK0") (class "Default")
      (node (ref "TP15") (pin "TP") (pinfunction "TP_TP") (pintype "input"))
      (node (ref "U$14") (pin "26") (pinfunction "P22/SCK0_26") (pintype "bidirectional"))
    )
    (net (code "54") (name "SCK1") (class "Default")
      (node (ref "JP1") (pin "1") (pinfunction "1_1") (pintype "passive"))
      (node (ref "TP10") (pin "TP") (pinfunction "TP_TP") (pintype "input"))
      (node (ref "U$14") (pin "21") (pinfunction "TCK/FINEC/P27/~{CS7}/MTIOC2B/TMCI3/PO7/SCK1/RSPCKB_21") (pintype "bidirectional"))
    )
    (net (code "55") (name "SCK3") (class "Default")
      (node (ref "TP13") (pin "TP") (pinfunction "TP_TP") (pintype "input"))
      (node (ref "U$14") (pin "24") (pinfunction "P24/~{CS4}/SCK3_24") (pintype "bidirectional"))
    )
    (net (code "56") (name "SCK5") (class "Default")
      (node (ref "TP37") (pin "TP") (pinfunction "TP_TP") (pintype "input"))
      (node (ref "U$14") (pin "69") (pinfunction "PA1/A1/SCK5/SSLA2/IRQ11_69") (pintype "bidirectional"))
    )
    (net (code "57") (name "SCK6") (class "Default")
      (node (ref "TP5") (pin "TP") (pinfunction "TP_TP") (pintype "input"))
      (node (ref "U$14") (pin "16") (pinfunction "~{TRST}/P34/MTIOC0A/TMCI3/PO12/~{POE2}/SCK6/SCK0/IRQ4_16") (pintype "bidirectional"))
    )
    (net (code "58") (name "SCK9") (class "Default")
      (node (ref "U$14") (pin "55") (pinfunction "PB5/A13/SCK9_55") (pintype "bidirectional"))
    )
    (net (code "59") (name "SCK12") (class "Default")
      (node (ref "TP29") (pin "TP") (pinfunction "TP_TP") (pintype "input"))
      (node (ref "U$14") (pin "78") (pinfunction "PE0/D8[A8/D8]/SCK12/SSLB1/ANEX0_78") (pintype "bidirectional"))
    )
    (net (code "60") (name "SCL0") (class "Default")
      (node (ref "TP21") (pin "TP") (pinfunction "TP_TP") (pintype "input"))
      (node (ref "U$14") (pin "34") (pinfunction "P12/RXD2/SMISO2/SSCL2/SCL0[FM+]/IRQ2_34") (pintype "bidirectional"))
    )
    (net (code "61") (name "SCL5") (class "Default")
      (node (ref "TP39") (pin "TP") (pinfunction "TP_TP") (pintype "input"))
      (node (ref "U$14") (pin "67") (pinfunction "PA3/A3/RXD5/SMISO5/SSCL5/IRQ6-DS_67") (pintype "bidirectional"))
    )
    (net (code "62") (name "SDA0") (class "Default")
      (node (ref "TP20") (pin "TP") (pinfunction "TP_TP") (pintype "input"))
      (node (ref "U$14") (pin "33") (pinfunction "P13/TXD2/SMOSI2/SSDA2/SDA0[FM+]/IRQ3/~{ADTRG}_33") (pintype "bidirectional"))
    )
    (net (code "63") (name "SMISO0") (class "Default")
      (node (ref "TP16") (pin "TP") (pinfunction "TP_TP") (pintype "input"))
      (node (ref "U$14") (pin "27") (pinfunction "P21/RXD0/SMISO0/SSCL0/IRQ9_27") (pintype "bidirectional"))
    )
    (net (code "64") (name "SMISO1") (class "Default")
      (node (ref "JP1") (pin "11") (pinfunction "11_11") (pintype "passive"))
      (node (ref "TP9") (pin "TP") (pinfunction "TP_TP") (pintype "input"))
      (node (ref "U$14") (pin "20") (pinfunction "P30/RXD1/SMISO1/SSCL1/MISOB/IRQ0-DS_20") (pintype "bidirectional"))
    )
    (net (code "65") (name "SMISO3") (class "Default")
      (node (ref "TP12") (pin "TP") (pinfunction "TP_TP") (pintype "input"))
      (node (ref "U$14") (pin "23") (pinfunction "P25/~{CS5}/RXD3/SMISO3/SSCL3/~{ADTRG0}_23") (pintype "bidirectional"))
    )
    (net (code "66") (name "SMISO5") (class "Default")
      (node (ref "TP38") (pin "TP") (pinfunction "TP_TP") (pintype "input"))
      (node (ref "U$14") (pin "68") (pinfunction "PA2/A2/PO18/RXD5/SMISO5/SSCL5/SSLA3_68") (pintype "bidirectional"))
    )
    (net (code "67") (name "SMISO6") (class "Default")
      (node (ref "TP6") (pin "TP") (pinfunction "TP_TP") (pintype "input"))
      (node (ref "U$14") (pin "17") (pinfunction "P33/MTIOC0D/TIOCD0/TMRI3/PO11/RXD6/RXD0/SMISO6/SMISO0/SSCL6/SSCL0/IRQ3-DS_17") (pintype "bidirectional"))
    )
    (net (code "68") (name "SMISO9") (class "Default")
      (node (ref "U$14") (pin "54") (pinfunction "PB6/A14/RXD9/SMISO9/SSCL9_54") (pintype "bidirectional"))
    )
    (net (code "69") (name "SMISO12") (class "Default")
      (node (ref "TP31") (pin "TP") (pinfunction "TP_TP") (pintype "input"))
      (node (ref "U$14") (pin "76") (pinfunction "PE2/D10[A10/D10]/RXD12/SMISO12/SSCL12/RXDX12/SSLB3/MOSIB/IRQ7-DS/AN0_76") (pintype "bidirectional"))
    )
    (net (code "70") (name "SMOSI0") (class "Default")
      (node (ref "TP17") (pin "TP") (pinfunction "TP_TP") (pintype "input"))
      (node (ref "U$14") (pin "28") (pinfunction "P20/TXD0/SMOSI0/SSDA0/IRQ8_28") (pintype "bidirectional"))
    )
    (net (code "71") (name "SMOSI3") (class "Default")
      (node (ref "TP14") (pin "TP") (pinfunction "TP_TP") (pintype "input"))
      (node (ref "U$14") (pin "25") (pinfunction "P23/TXD3/~{CTS0}/~{RTS0}/SMOSI3/~{SS0}/SSDA3_25") (pintype "bidirectional"))
    )
    (net (code "72") (name "SMOSI5") (class "Default")
      (node (ref "TP40") (pin "TP") (pinfunction "TP_TP") (pintype "input"))
      (node (ref "U$14") (pin "66") (pinfunction "PA4/A4/TXD5/SMOSI5/SSDA5/SSLA0/IRQ5-DS_66") (pintype "bidirectional"))
    )
    (net (code "73") (name "SMOSI6") (class "Default")
      (node (ref "TP7") (pin "TP") (pinfunction "TP_TP") (pintype "input"))
      (node (ref "U$14") (pin "18") (pinfunction "P32/TXD6/TXD0/SMOSI6/SMOSI0/SSDA6/SSDA0/IRQ3-DS_18") (pintype "bidirectional"))
    )
    (net (code "74") (name "SMOSI9") (class "Default")
      (node (ref "U$14") (pin "53") (pinfunction "PB7/A15/TXD9/SMOSI9/SSDA9_53") (pintype "bidirectional"))
    )
    (net (code "75") (name "SMOSI12") (class "Default")
      (node (ref "TP30") (pin "TP") (pinfunction "TP_TP") (pintype "input"))
      (node (ref "U$14") (pin "77") (pinfunction "PE1/D9[A9/D9]/TXD12/SMOSI12/SSDA12/TXDX12/SIOX12/SSLB2/RSPCKB/ANEX1_77") (pintype "bidirectional"))
    )
    (net (code "76") (name "USB0_DM") (class "Default")
      (node (ref "R7") (pin "1") (pinfunction "1_1") (pintype "passive"))
      (node (ref "U$14") (pin "36") (pinfunction "USB0_DM_36") (pintype "bidirectional"))
    )
    (net (code "77") (name "USB0_DP") (class "Default")
      (node (ref "R10") (pin "2") (pinfunction "2_2") (pintype "passive"))
      (node (ref "R8") (pin "1") (pinfunction "1_1") (pintype "passive"))
      (node (ref "U$14") (pin "37") (pinfunction "USB0_DP_37") (pintype "bidirectional"))
    )
    (net (code "78") (name "V+") (class "Default")
      (node (ref "R50") (pin "1") (pinfunction "1_1") (pintype "passive"))
      (node (ref "TP49") (pin "TP") (pinfunction "TP_TP") (pintype "input"))
    )
    (net (code "79") (name "VBAT0_AD") (class "Default")
      (node (ref "C15") (pin "1") (pinfunction "1_1") (pintype "passive"))
      (node (ref "R16") (pin "2") (pinfunction "2_2") (pintype "passive"))
      (node (ref "R17") (pin "1") (pinfunction "1_1") (pintype "passive"))
      (node (ref "U$14") (pin "95") (pinfunction "P40/IRQ8-DS/AN000_95") (pintype "bidirectional"))
    )
    (net (code "80") (name "VBAT1_AD") (class "Default")
      (node (ref "C8") (pin "1") (pinfunction "1_1") (pintype "passive"))
      (node (ref "R11") (pin "2") (pinfunction "2_2") (pintype "passive"))
      (node (ref "R13") (pin "1") (pinfunction "1_1") (pintype "passive"))
      (node (ref "U$14") (pin "93") (pinfunction "P41/IRQ9-DS/AN001_93") (pintype "bidirectional"))
    )
    (net (code "81") (name "VBAT2_AD") (class "Default")
      (node (ref "C2") (pin "1") (pinfunction "1_1") (pintype "passive"))
      (node (ref "R3") (pin "2") (pinfunction "2_2") (pintype "passive"))
      (node (ref "R4") (pin "1") (pinfunction "1_1") (pintype "passive"))
      (node (ref "U$14") (pin "92") (pinfunction "P42/IRQ10-DS/AN002_92") (pintype "bidirectional"))
    )
    (net (code "82") (name "VBAT3_AD") (class "Default")
      (node (ref "C1") (pin "1") (pinfunction "1_1") (pintype "passive"))
      (node (ref "R1") (pin "2") (pinfunction "2_2") (pintype "passive"))
      (node (ref "R2") (pin "1") (pinfunction "1_1") (pintype "passive"))
      (node (ref "U$14") (pin "91") (pinfunction "P43/IRQ11-DS/AN003_91") (pintype "bidirectional"))
    )
    (net (code "83") (name "VBATT") (class "Default")
      (node (ref "D1") (pin "3") (pinfunction "C_3") (pintype "passive"))
      (node (ref "TP3") (pin "TP") (pinfunction "TP_TP") (pintype "input"))
      (node (ref "U$14") (pin "6") (pinfunction "VBATT_6") (pintype "bidirectional"))
      (node (ref "U$2") (pin "P") (pinfunction "P_P") (pintype "bidirectional"))
    )
    (net (code "84") (name "VBUS") (class "Default")
      (node (ref "CN1") (pin "VBUS") (pinfunction "VBUS_VBUS") (pintype "power_in"))
      (node (ref "D2") (pin "A") (pinfunction "A_A") (pintype "passive"))
      (node (ref "R14") (pin "1") (pinfunction "1_1") (pintype "passive"))
    )
    (net (code "85") (name "XCIN") (class "Default")
      (node (ref "C9") (pin "2") (pinfunction "2_2") (pintype "passive"))
      (node (ref "Q1") (pin "1") (pinfunction "1_1") (pintype "passive"))
      (node (ref "U$14") (pin "8") (pinfunction "XCIN_8") (pintype "bidirectional"))
    )
    (net (code "86") (name "XCOUT") (class "Default")
      (node (ref "C11") (pin "2") (pinfunction "2_2") (pintype "passive"))
      (node (ref "Q1") (pin "4") (pinfunction "2_4") (pintype "passive"))
      (node (ref "U$14") (pin "9") (pinfunction "XCOUT_9") (pintype "bidirectional"))
    )
    (net (code "87") (name "XTAL") (class "Default")
      (node (ref "C6") (pin "2") (pinfunction "2_2") (pintype "passive"))
      (node (ref "U$14") (pin "11") (pinfunction "XTAL/P37_11") (pintype "bidirectional"))
      (node (ref "X1") (pin "P$1") (pinfunction "P$1_P$1") (pintype "bidirectional"))
    )
    (net (code "88") (name "unconnected-(CN1-PadID)") (class "Default")
      (node (ref "CN1") (pin "ID") (pinfunction "ID_ID") (pintype "bidirectional"))
    )
    (net (code "89") (name "unconnected-(JP1-Pad3)") (class "Default")
      (node (ref "JP1") (pin "3") (pinfunction "3_3") (pintype "passive"))
    )
    (net (code "90") (name "unconnected-(U$1-NC-PadP$3)") (class "Default")
      (node (ref "U$1") (pin "P$3") (pinfunction "NC_P$3") (pintype "bidirectional"))
    )
    (net (code "91") (name "unconnected-(U$14-BCLK{slash}P53-Pad41)") (class "Default")
      (node (ref "U$14") (pin "41") (pinfunction "BCLK/P53_41") (pintype "bidirectional"))
    )
    (net (code "92") (name "unconnected-(U$14-PB0{slash}A8{slash}RXD6{slash}SMISO6{slash}SSCL6{slash}RSPCKA{slash}IRQ12-Pad61)") (class "Default")
      (node (ref "U$14") (pin "61") (pinfunction "PB0/A8/RXD6/SMISO6/SSCL6/RSPCKA/IRQ12_61") (pintype "bidirectional"))
    )
    (net (code "93") (name "unconnected-(U$14-PB1{slash}A9{slash}TXD6{slash}SMOSI6{slash}SSDA6{slash}IRQ4-DS-Pad59)") (class "Default")
      (node (ref "U$14") (pin "59") (pinfunction "PB1/A9/TXD6/SMOSI6/SSDA6/IRQ4-DS_59") (pintype "bidirectional"))
    )
    (net (code "94") (name "unconnected-(U$14-PB2{slash}A10{slash}~{CTS6}{slash}~{RTS6}{slash}~{SS6}-Pad58)") (class "Default")
      (node (ref "U$14") (pin "58") (pinfunction "PB2/A10/~{CTS6}/~{RTS6}/~{SS6}_58") (pintype "bidirectional"))
    )
    (net (code "95") (name "unconnected-(U$14-PB3{slash}A11{slash}SCK6-Pad57)") (class "Default")
      (node (ref "U$14") (pin "57") (pinfunction "PB3/A11/SCK6_57") (pintype "bidirectional"))
    )
    (net (code "96") (name "unconnected-(U$14-PC0{slash}A16{slash}~{CTS5}{slash}~{RTS5}{slash}~{SS5}{slash}SSLA1{slash}IRQ14-Pad52)") (class "Default")
      (node (ref "U$14") (pin "52") (pinfunction "PC0/A16/~{CTS5}/~{RTS5}/~{SS5}/SSLA1/IRQ14_52") (pintype "bidirectional"))
    )
    (net (code "97") (name "unconnected-(U$14-PC1{slash}A17{slash}SCK5{slash}SSLA2{slash}IRQ12-Pad51)") (class "Default")
      (node (ref "U$14") (pin "51") (pinfunction "PC1/A17/SCK5/SSLA2/IRQ12_51") (pintype "bidirectional"))
    )
    (net (code "98") (name "~{OLED_CS}") (class "Default")
      (node (ref "JP1") (pin "10") (pinfunction "10_10") (pintype "passive"))
      (node (ref "TP24") (pin "TP") (pinfunction "TP_TP") (pintype "input"))
      (node (ref "U$1") (pin "P$16") (pinfunction "~{CS}_P$16") (pintype "bidirectional"))
      (node (ref "U$14") (pin "46") (pinfunction "PC6/A22/~{CS1}/RXD8/SMISO8/SSCL8/MOSIA/IRQ13_46") (pintype "bidirectional"))
    )
    (net (code "99") (name "~{OLED_DC}") (class "Default")
      (node (ref "R9") (pin "2") (pinfunction "2_2") (pintype "passive"))
      (node (ref "U$1") (pin "P$14") (pinfunction "~{DC}_P$14") (pintype "bidirectional"))
      (node (ref "U$14") (pin "45") (pinfunction "PC7/A23/~{CS0}/TXD8/SMOSI8/SSDA8/MISOA/IRQ14_45") (pintype "bidirectional"))
    )
    (net (code "100") (name "~{OLED_RD}") (class "Default")
      (node (ref "U$1") (pin "P$12") (pinfunction "~{RD}_P$12") (pintype "bidirectional"))
      (node (ref "U$14") (pin "42") (pinfunction "P52/~{RD}/RXD2/SMISO2/SSCL2/SSLB3_42") (pintype "bidirectional"))
    )
    (net (code "101") (name "~{OLED_RESET}") (class "Default")
      (node (ref "U$1") (pin "P$15") (pinfunction "~{RESET}_P$15") (pintype "bidirectional"))
      (node (ref "U$14") (pin "43") (pinfunction "P51/~{WR1}/~{BC1}/~{WAIT}/SCK2/SSLB2_43") (pintype "bidirectional"))
    )
    (net (code "102") (name "~{OLED_WR}") (class "Default")
      (node (ref "U$1") (pin "P$13") (pinfunction "~{WR}_P$13") (pintype "bidirectional"))
      (node (ref "U$14") (pin "44") (pinfunction "P50/~{WR0}/~{WR}/TXD2/SMOSI2/SSDA2/SSLB1_44") (pintype "bidirectional"))
    )
    (net (code "103") (name "~{RESET}") (class "Default")
      (node (ref "IC2") (pin "2") (pinfunction "~{RESET}_2") (pintype "input"))
      (node (ref "JP1") (pin "13") (pinfunction "13_13") (pintype "passive"))
      (node (ref "R18") (pin "2") (pinfunction "2_2") (pintype "passive"))
      (node (ref "S3") (pin "3") (pinfunction "P_3") (pintype "passive"))
      (node (ref "S3") (pin "4") (pinfunction "P1_4") (pintype "passive"))
      (node (ref "U$14") (pin "10") (pinfunction "~{RES}_10") (pintype "bidirectional"))
    )
    (net (code "104") (name "~{SS1}") (class "Default")
      (node (ref "JP1") (pin "9") (pinfunction "9_9") (pintype "passive"))
      (node (ref "TP8") (pin "TP") (pinfunction "TP_TP") (pintype "input"))
      (node (ref "U$14") (pin "19") (pinfunction "~{CTS1}/~{RTS1}/~{SS1}/SSLB0/IRQ1-DS_19") (pintype "bidirectional"))
    )
    (net (code "105") (name "~{SS3}") (class "Default")
      (node (ref "JP1") (pin "5") (pinfunction "5_5") (pintype "passive"))
      (node (ref "TP11") (pin "TP") (pinfunction "TP_TP") (pintype "input"))
      (node (ref "U$14") (pin "22") (pinfunction "TDO/P26/~{CS6}/TXD1/~{CTS3}/~{RTS3}/SMOSI1/~{SS3}/SSDA1/MOSIB_22") (pintype "bidirectional"))
    )
    (net (code "106") (name "~{SS5}") (class "Default")
      (node (ref "TP42") (pin "TP") (pinfunction "TP_TP") (pintype "input"))
      (node (ref "U$14") (pin "64") (pinfunction "PA6/A6/~{CTS5}/~{RTS5}/~{SS5}/MOSIA_64") (pintype "bidirectional"))
    )
    (net (code "107") (name "~{SS9}") (class "Default")
      (node (ref "U$14") (pin "56") (pinfunction "PB4/A12/~{CTS9}/~{RTS9}/~{SS9}_56") (pintype "bidirectional"))
    )
    (net (code "108") (name "~{SS12}") (class "Default")
      (node (ref "TP32") (pin "TP") (pinfunction "TP_TP") (pintype "input"))
      (node (ref "U$14") (pin "75") (pinfunction "PE3/D11[A11/D11]/~{CTS12}/~{RTS12}/~{SS12}/MISOB/AN1_75") (pintype "bidirectional"))
    )
  )
)
